# Interface_CAN.net
KiCad netlist of a schematic drawn in Altium Designer
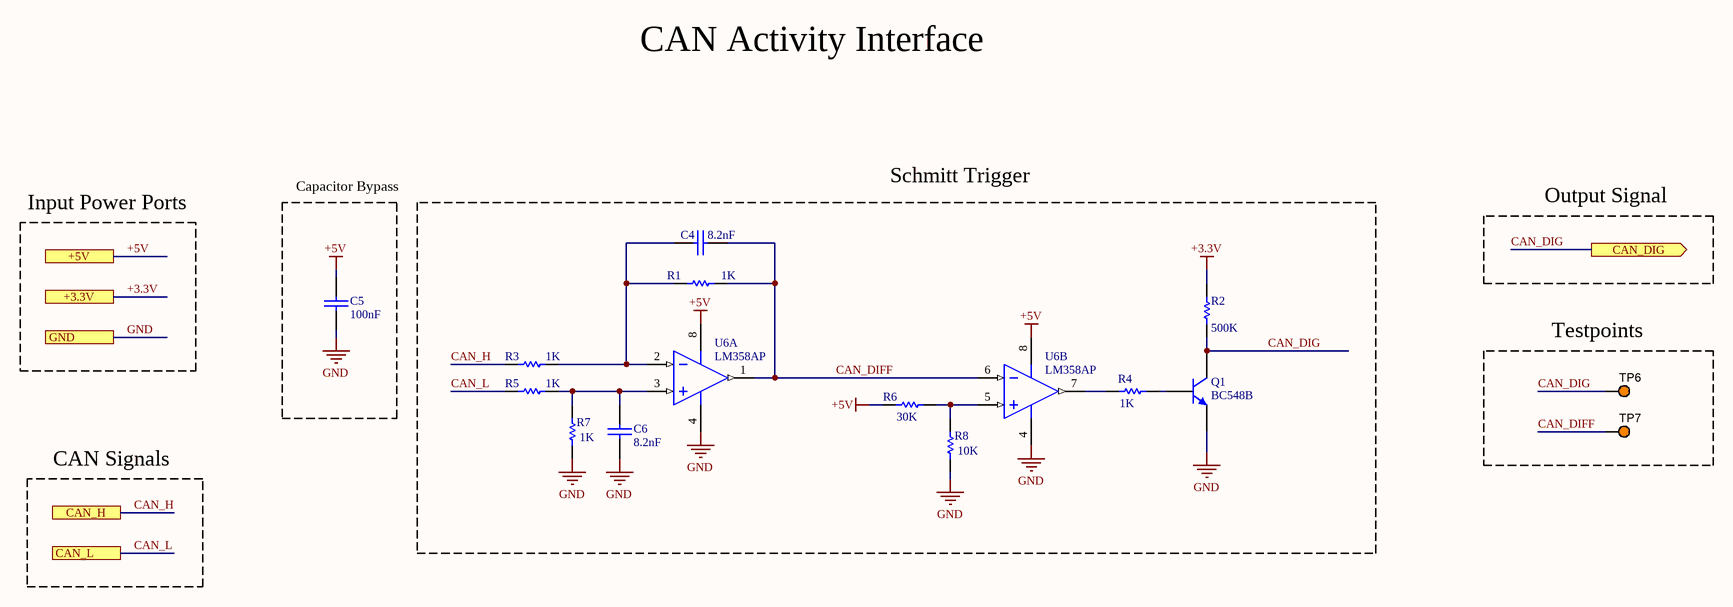
[diagram p0: Interface_CAN.SchDoc]

(export (version "E")
  (design (tool "Eeschema 10.0.6"))
  (components
    (comp (ref "C4") (value "8.2nF") (footprint "CAP200") (libsource (lib "LIBEBAL") (part "CAP")))
    (comp (ref "C5") (value "100nF") (footprint "CAP200") (libsource (lib "LIBEBAL") (part "CAP")))
    (comp (ref "C6") (value "8.2nF") (footprint "CAP200") (libsource (lib "LIBEBAL") (part "CAP")))
    (comp (ref "Q1")
      (value "BC548B")
      (footprint "TO-226-AA")
      (description "NPN Bipolar Transistor")
      (fields (field (name "PUBLISHER") "Altium Limited"))
      (libsource (lib "Miscellaneous Devices") (part "NPN"))
    )
    (comp (ref "R1")
      (value "1K")
      (footprint "AXIAL-0.3")
      (description "Resistor")
      (fields (field (name "Comment") "Res1") (field (name "PUBLISHER") "Altium Limited"))
      (libsource (lib "Miscellaneous Devices") (part "Res1"))
    )
    (comp (ref "R2")
      (value "500K")
      (footprint "AXIAL-0.3")
      (description "Resistor")
      (fields (field (name "Comment") "Res1") (field (name "PUBLISHER") "Altium Limited"))
      (libsource (lib "Miscellaneous Devices") (part "Res1"))
    )
    (comp (ref "R3")
      (value "1K")
      (footprint "AXIAL-0.3")
      (description "Resistor")
      (fields (field (name "Comment") "Res1") (field (name "PUBLISHER") "Altium Limited"))
      (libsource (lib "Miscellaneous Devices") (part "Res1"))
    )
    (comp (ref "R4")
      (value "1K")
      (footprint "AXIAL-0.3")
      (description "Resistor")
      (fields (field (name "Comment") "Res1") (field (name "PUBLISHER") "Altium Limited"))
      (libsource (lib "Miscellaneous Devices") (part "Res1"))
    )
    (comp (ref "R5")
      (value "1K")
      (footprint "AXIAL-0.3")
      (description "Resistor")
      (fields (field (name "Comment") "Res1") (field (name "PUBLISHER") "Altium Limited"))
      (libsource (lib "Miscellaneous Devices") (part "Res1"))
    )
    (comp (ref "R6")
      (value "30K")
      (footprint "AXIAL-0.3")
      (description "Resistor")
      (fields (field (name "Comment") "Res1") (field (name "PUBLISHER") "Altium Limited"))
      (libsource (lib "Miscellaneous Devices") (part "Res1"))
    )
    (comp (ref "R7")
      (value "1K")
      (footprint "AXIAL-0.3")
      (description "Resistor")
      (fields (field (name "Comment") "Res1") (field (name "PUBLISHER") "Altium Limited"))
      (libsource (lib "Miscellaneous Devices") (part "Res1"))
    )
    (comp (ref "R8")
      (value "10K")
      (footprint "AXIAL-0.3")
      (description "Resistor")
      (fields (field (name "Comment") "Res1") (field (name "PUBLISHER") "Altium Limited"))
      (libsource (lib "Miscellaneous Devices") (part "Res1"))
    )
    (comp (ref "TP6")
      (value "5003")
      (footprint "KSTN-5003")
      (description "Test Point, Orange, Height 4.6 mm, Tail Length 3 mm, 1-Pin THD, RoHS")
      (fields (field (name "MANUFACTURER") "Keystone"))
      (libsource (lib "TD") (part "TESTPOINT_ORANGE"))
    )
    (comp (ref "TP7")
      (value "5003")
      (footprint "KSTN-5003")
      (description "Test Point, Orange, Height 4.6 mm, Tail Length 3 mm, 1-Pin THD, RoHS")
      (fields (field (name "MANUFACTURER") "Keystone"))
      (libsource (lib "TD") (part "TESTPOINT_ORANGE"))
    )
    (comp (ref "U6")
      (value "LM358AP")
      (footprint "P0008A")
      (description "Dual Operational Amplifier, 3 to 32 V, 0 to 70 degC, 8-Pin PDIP (P), Pb-Free (RoHS), Tube")
      (fields (field (name "MANUFACTURER") "Texas Instruments (TI)"))
      (libsource (lib "TD") (part "TI-LM358-8"))
    )
  )
  (nets
    (net (code "1") (name "+3.3V") (class "Default")
      (node (ref "R2") (pin "2") (pinfunction "2_2") (pintype "passive"))
    )
    (net (code "2") (name "+5V") (class "Default")
      (node (ref "C5") (pin "1") (pinfunction "1_1") (pintype "passive"))
      (node (ref "R6") (pin "1") (pinfunction "1_1") (pintype "passive"))
      (node (ref "U6") (pin "8") (pinfunction "VCC_8") (pintype "power_in"))
    )
    (net (code "3") (name "/CAN_DIFF") (class "Default")
      (node (ref "C4") (pin "2") (pinfunction "2_2") (pintype "passive"))
      (node (ref "R1") (pin "2") (pinfunction "2_2") (pintype "passive"))
      (node (ref "TP7") (pin "1") (pinfunction "1_1") (pintype "passive"))
      (node (ref "U6") (pin "1") (pinfunction "1OUT_1") (pintype "output"))
      (node (ref "U6") (pin "6") (pinfunction "2IN-_6") (pintype "input"))
    )
    (net (code "4") (name "/CAN_DIG") (class "Default")
      (node (ref "Q1") (pin "1") (pinfunction "C_1") (pintype "passive"))
      (node (ref "R2") (pin "1") (pinfunction "1_1") (pintype "passive"))
      (node (ref "TP6") (pin "1") (pinfunction "1_1") (pintype "passive"))
    )
    (net (code "5") (name "/CAN_H") (class "Default")
      (node (ref "R3") (pin "1") (pinfunction "1_1") (pintype "passive"))
    )
    (net (code "6") (name "/CAN_L") (class "Default")
      (node (ref "R5") (pin "1") (pinfunction "1_1") (pintype "passive"))
    )
    (net (code "7") (name "GND") (class "Default")
      (node (ref "C5") (pin "2") (pinfunction "2_2") (pintype "passive"))
      (node (ref "C6") (pin "2") (pinfunction "2_2") (pintype "passive"))
      (node (ref "Q1") (pin "3") (pinfunction "E_3") (pintype "passive"))
      (node (ref "R7") (pin "1") (pinfunction "1_1") (pintype "passive"))
      (node (ref "R8") (pin "2") (pinfunction "2_2") (pintype "passive"))
      (node (ref "U6") (pin "4") (pinfunction "GND_4") (pintype "power_in"))
    )
    (net (code "8") (name "Net-(Q1-B)") (class "Default")
      (node (ref "Q1") (pin "2") (pinfunction "B_2") (pintype "passive"))
      (node (ref "R4") (pin "2") (pinfunction "2_2") (pintype "passive"))
    )
    (net (code "9") (name "Net-(U6A-1IN+)") (class "Default")
      (node (ref "C6") (pin "1") (pinfunction "1_1") (pintype "passive"))
      (node (ref "R5") (pin "2") (pinfunction "2_2") (pintype "passive"))
      (node (ref "R7") (pin "2") (pinfunction "2_2") (pintype "passive"))
      (node (ref "U6") (pin "3") (pinfunction "1IN+_3") (pintype "input"))
    )
    (net (code "10") (name "Net-(U6A-1IN-)") (class "Default")
      (node (ref "C4") (pin "1") (pinfunction "1_1") (pintype "passive"))
      (node (ref "R1") (pin "1") (pinfunction "1_1") (pintype "passive"))
      (node (ref "R3") (pin "2") (pinfunction "2_2") (pintype "passive"))
      (node (ref "U6") (pin "2") (pinfunction "1IN-_2") (pintype "input"))
    )
    (net (code "11") (name "Net-(U6B-2IN+)") (class "Default")
      (node (ref "R6") (pin "2") (pinfunction "2_2") (pintype "passive"))
      (node (ref "R8") (pin "1") (pinfunction "1_1") (pintype "passive"))
      (node (ref "U6") (pin "5") (pinfunction "2IN+_5") (pintype "input"))
    )
    (net (code "12") (name "Net-(U6B-2OUT)") (class "Default")
      (node (ref "R4") (pin "1") (pinfunction "1_1") (pintype "passive"))
      (node (ref "U6") (pin "7") (pinfunction "2OUT_7") (pintype "output"))
    )
  )
)
